# station_v2_3.net
KiCad netlist of a schematic drawn in EAGLE
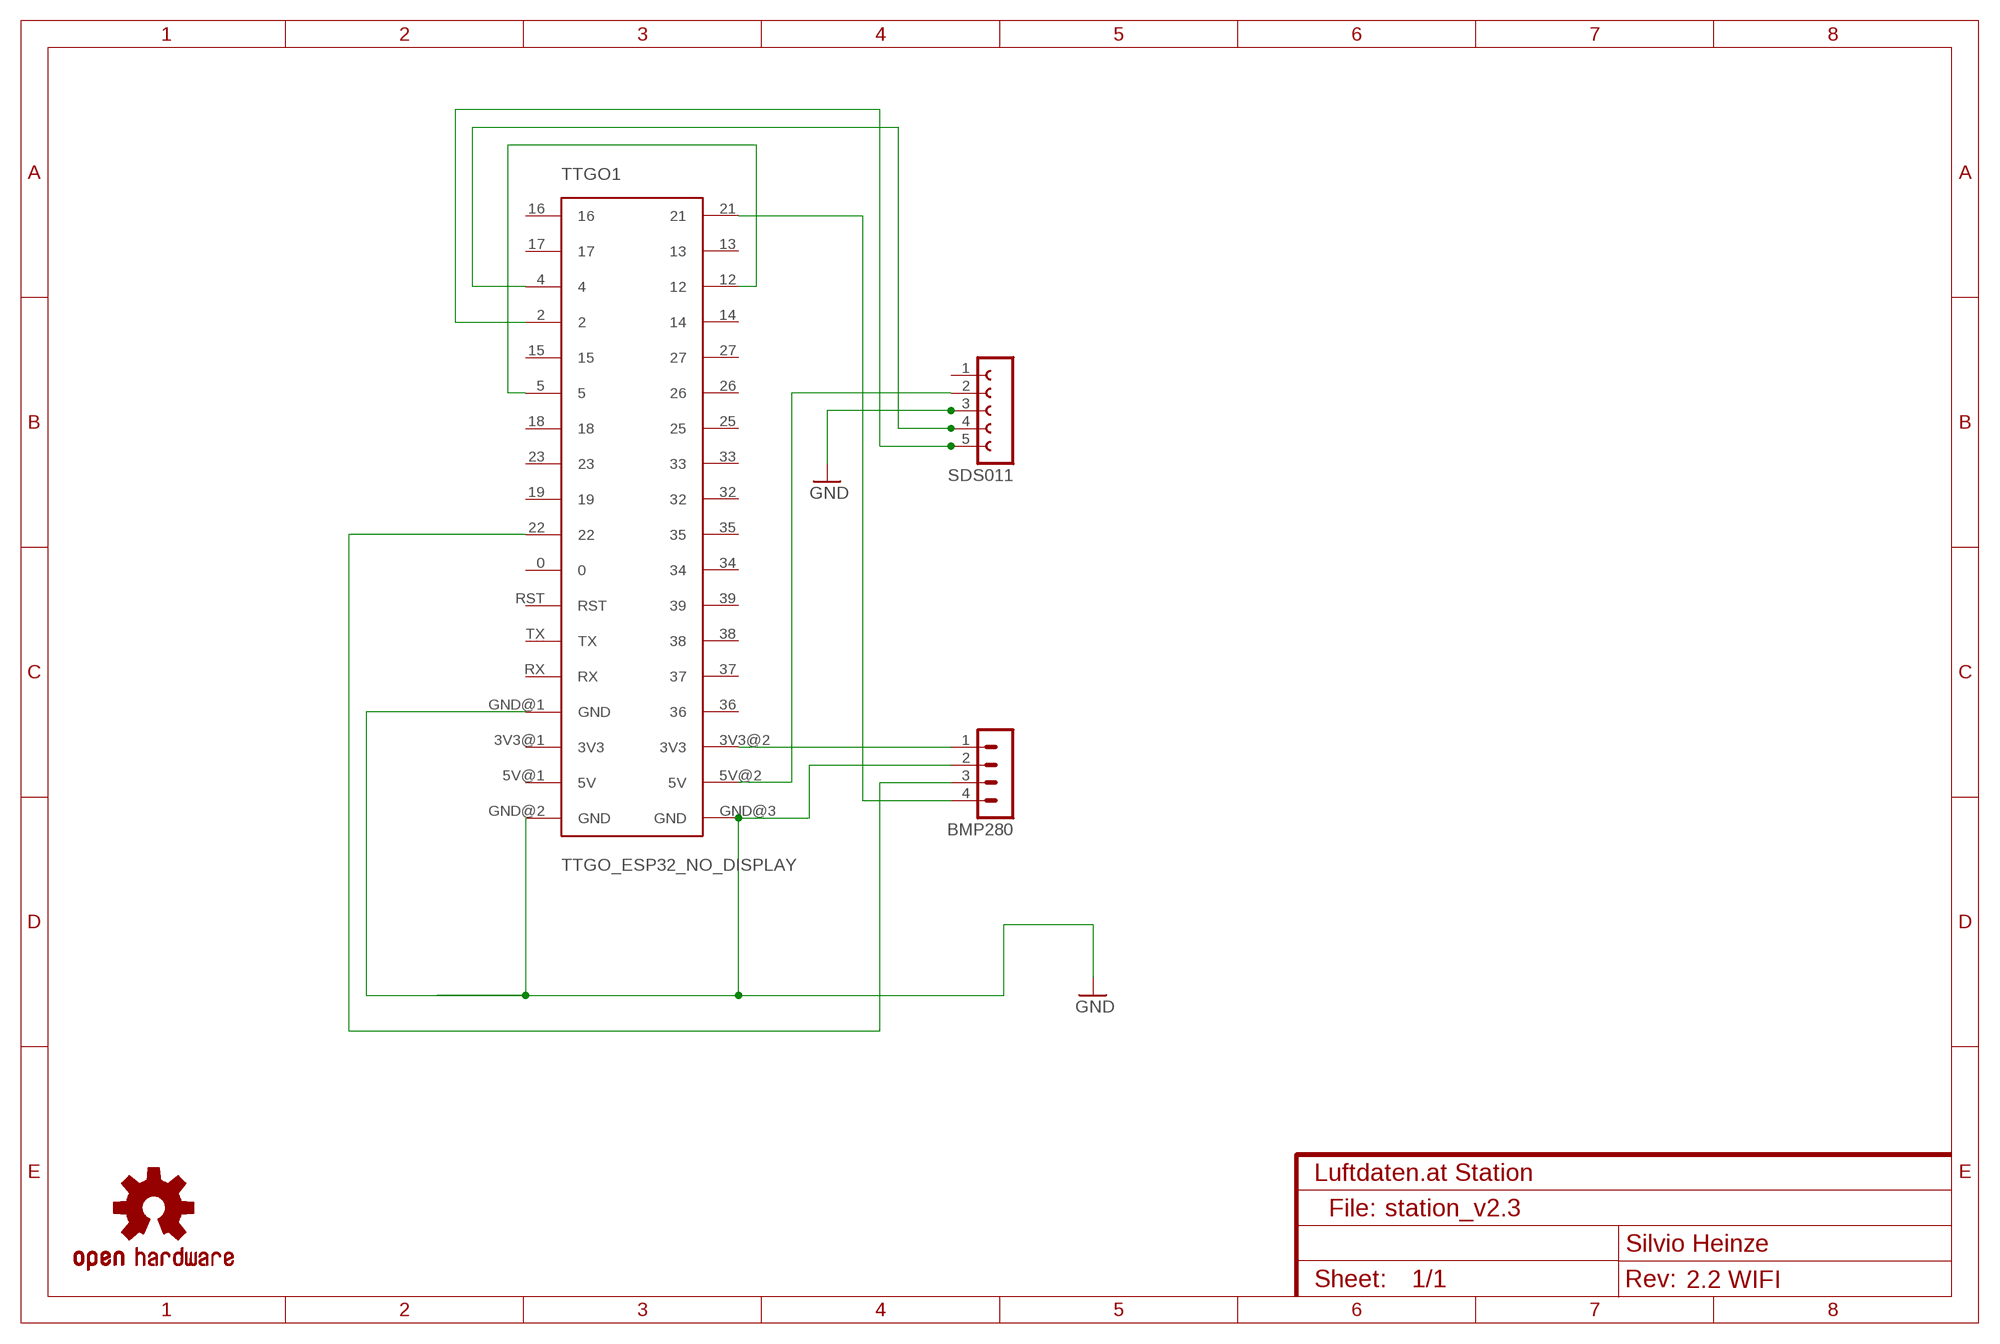
[diagram p0: schematic, sheet 1]

(export (version "E")
  (design (tool "Eeschema 10.0.6"))
  (components
    (comp (ref "BMP280")
      (value "MA04-1")
      (footprint "eagle-import:MA04-1")
      (libsource (lib "eagle-import") (part "MA04-1"))
    )
    (comp (ref "LOGO2")
      (value "OSHW-LOGOM")
      (footprint "eagle-import:OSHW-LOGO-M")
      (libsource (lib "eagle-import") (part "OSHW-LOGOM"))
    )
    (comp (ref "SDS011")
      (value "FE05-1")
      (footprint "eagle-import:FE05-1")
      (libsource (lib "eagle-import") (part "FE05-1"))
    )
    (comp (ref "TTGO1")
      (value "TTGO_ESP32_NO_DISPLAY")
      (footprint "eagle-import:TTGO_ESP32_NO_DISPLAY")
      (libsource (lib "eagle-import") (part "TTGO_ESP32_NO_DISPLAY"))
    )
  )
  (nets
    (net (code "1") (name "GND") (class "Default")
      (node (ref "BMP280") (pin "2") (pinfunction "2_2") (pintype "passive"))
      (node (ref "SDS011") (pin "3") (pinfunction "3_3") (pintype "passive"))
      (node (ref "TTGO1") (pin "GND@1") (pinfunction "GND_GND@1") (pintype "bidirectional"))
      (node (ref "TTGO1") (pin "GND@2") (pinfunction "GND_GND@2") (pintype "bidirectional"))
      (node (ref "TTGO1") (pin "GND@3") (pinfunction "GND_GND@3") (pintype "bidirectional"))
    )
    (net (code "2") (name "Net-(BMP280-Pad1)") (class "Default")
      (node (ref "BMP280") (pin "1") (pinfunction "1_1") (pintype "passive"))
      (node (ref "TTGO1") (pin "3V3@2") (pinfunction "3V3_3V3@2") (pintype "bidirectional"))
    )
    (net (code "3") (name "Net-(BMP280-Pad3)") (class "Default")
      (node (ref "BMP280") (pin "3") (pinfunction "3_3") (pintype "passive"))
      (node (ref "TTGO1") (pin "22") (pinfunction "22_22") (pintype "bidirectional"))
    )
    (net (code "4") (name "Net-(BMP280-Pad4)") (class "Default")
      (node (ref "BMP280") (pin "4") (pinfunction "4_4") (pintype "passive"))
      (node (ref "TTGO1") (pin "21") (pinfunction "21_21") (pintype "bidirectional"))
    )
    (net (code "5") (name "Net-(SDS011-Pad2)") (class "Default")
      (node (ref "SDS011") (pin "2") (pinfunction "2_2") (pintype "passive"))
      (node (ref "TTGO1") (pin "5V@2") (pinfunction "5V_5V@2") (pintype "bidirectional"))
    )
    (net (code "6") (name "Net-(SDS011-Pad4)") (class "Default")
      (node (ref "SDS011") (pin "4") (pinfunction "4_4") (pintype "passive"))
      (node (ref "TTGO1") (pin "4") (pinfunction "4_4") (pintype "bidirectional"))
    )
    (net (code "7") (name "Net-(SDS011-Pad5)") (class "Default")
      (node (ref "SDS011") (pin "5") (pinfunction "5_5") (pintype "passive"))
      (node (ref "TTGO1") (pin "2") (pinfunction "2_2") (pintype "bidirectional"))
    )
    (net (code "8") (name "Net-(TTGO1-Pad12)") (class "Default")
      (node (ref "TTGO1") (pin "12") (pinfunction "12_12") (pintype "bidirectional"))
      (node (ref "TTGO1") (pin "5") (pinfunction "5_5") (pintype "bidirectional"))
    )
    (net (code "9") (name "unconnected-(SDS011-Pad1)") (class "Default")
      (node (ref "SDS011") (pin "1") (pinfunction "1_1") (pintype "passive"))
    )
    (net (code "10") (name "unconnected-(TTGO1-3V3-Pad3V3@1)") (class "Default")
      (node (ref "TTGO1") (pin "3V3@1") (pinfunction "3V3_3V3@1") (pintype "bidirectional"))
    )
    (net (code "11") (name "unconnected-(TTGO1-5V-Pad5V@1)") (class "Default")
      (node (ref "TTGO1") (pin "5V@1") (pinfunction "5V_5V@1") (pintype "bidirectional"))
    )
    (net (code "12") (name "unconnected-(TTGO1-Pad0)") (class "Default")
      (node (ref "TTGO1") (pin "0") (pinfunction "0_0") (pintype "bidirectional"))
    )
    (net (code "13") (name "unconnected-(TTGO1-Pad13)") (class "Default")
      (node (ref "TTGO1") (pin "13") (pinfunction "13_13") (pintype "bidirectional"))
    )
    (net (code "14") (name "unconnected-(TTGO1-Pad14)") (class "Default")
      (node (ref "TTGO1") (pin "14") (pinfunction "14_14") (pintype "bidirectional"))
    )
    (net (code "15") (name "unconnected-(TTGO1-Pad15)") (class "Default")
      (node (ref "TTGO1") (pin "15") (pinfunction "15_15") (pintype "bidirectional"))
    )
    (net (code "16") (name "unconnected-(TTGO1-Pad16)") (class "Default")
      (node (ref "TTGO1") (pin "16") (pinfunction "16_16") (pintype "bidirectional"))
    )
    (net (code "17") (name "unconnected-(TTGO1-Pad17)") (class "Default")
      (node (ref "TTGO1") (pin "17") (pinfunction "17_17") (pintype "bidirectional"))
    )
    (net (code "18") (name "unconnected-(TTGO1-Pad18)") (class "Default")
      (node (ref "TTGO1") (pin "18") (pinfunction "18_18") (pintype "bidirectional"))
    )
    (net (code "19") (name "unconnected-(TTGO1-Pad19)") (class "Default")
      (node (ref "TTGO1") (pin "19") (pinfunction "19_19") (pintype "bidirectional"))
    )
    (net (code "20") (name "unconnected-(TTGO1-Pad23)") (class "Default")
      (node (ref "TTGO1") (pin "23") (pinfunction "23_23") (pintype "bidirectional"))
    )
    (net (code "21") (name "unconnected-(TTGO1-Pad25)") (class "Default")
      (node (ref "TTGO1") (pin "25") (pinfunction "25_25") (pintype "bidirectional"))
    )
    (net (code "22") (name "unconnected-(TTGO1-Pad26)") (class "Default")
      (node (ref "TTGO1") (pin "26") (pinfunction "26_26") (pintype "bidirectional"))
    )
    (net (code "23") (name "unconnected-(TTGO1-Pad27)") (class "Default")
      (node (ref "TTGO1") (pin "27") (pinfunction "27_27") (pintype "bidirectional"))
    )
    (net (code "24") (name "unconnected-(TTGO1-Pad32)") (class "Default")
      (node (ref "TTGO1") (pin "32") (pinfunction "32_32") (pintype "bidirectional"))
    )
    (net (code "25") (name "unconnected-(TTGO1-Pad33)") (class "Default")
      (node (ref "TTGO1") (pin "33") (pinfunction "33_33") (pintype "bidirectional"))
    )
    (net (code "26") (name "unconnected-(TTGO1-Pad34)") (class "Default")
      (node (ref "TTGO1") (pin "34") (pinfunction "34_34") (pintype "bidirectional"))
    )
    (net (code "27") (name "unconnected-(TTGO1-Pad35)") (class "Default")
      (node (ref "TTGO1") (pin "35") (pinfunction "35_35") (pintype "bidirectional"))
    )
    (net (code "28") (name "unconnected-(TTGO1-Pad36)") (class "Default")
      (node (ref "TTGO1") (pin "36") (pinfunction "36_36") (pintype "bidirectional"))
    )
    (net (code "29") (name "unconnected-(TTGO1-Pad37)") (class "Default")
      (node (ref "TTGO1") (pin "37") (pinfunction "37_37") (pintype "bidirectional"))
    )
    (net (code "30") (name "unconnected-(TTGO1-Pad38)") (class "Default")
      (node (ref "TTGO1") (pin "38") (pinfunction "38_38") (pintype "bidirectional"))
    )
    (net (code "31") (name "unconnected-(TTGO1-Pad39)") (class "Default")
      (node (ref "TTGO1") (pin "39") (pinfunction "39_39") (pintype "bidirectional"))
    )
    (net (code "32") (name "unconnected-(TTGO1-PadRST)") (class "Default")
      (node (ref "TTGO1") (pin "RST") (pinfunction "RST_RST") (pintype "bidirectional"))
    )
    (net (code "33") (name "unconnected-(TTGO1-PadRX)") (class "Default")
      (node (ref "TTGO1") (pin "RX") (pinfunction "RX_RX") (pintype "bidirectional"))
    )
    (net (code "34") (name "unconnected-(TTGO1-PadTX)") (class "Default")
      (node (ref "TTGO1") (pin "TX") (pinfunction "TX_TX") (pintype "bidirectional"))
    )
  )
)
